# RGB_module.net
KiCad netlist of a schematic drawn in EAGLE
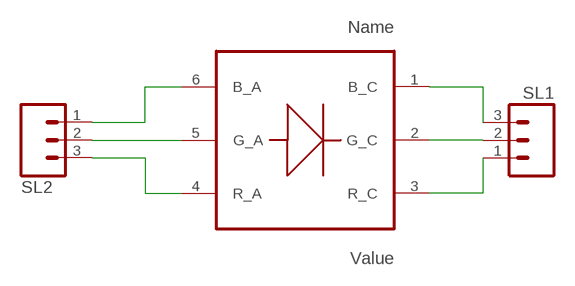
[diagram p0: schematic, sheet 1]

(export (version "E")
  (design (tool "Eeschema 10.0.6"))
  (components
    (comp (ref "RGB_MODULE")
      (value "RGB_SMD_3W")
      (footprint "eagle-import:RGB_SMD_6PIN")
      (libsource (lib "eagle-import") (part "RGB_SMD_3W"))
    )
    (comp (ref "SL1")
      (value "M03")
      (footprint "eagle-import:03P")
      (libsource (lib "eagle-import") (part "M03"))
    )
    (comp (ref "SL2")
      (value "M03")
      (footprint "eagle-import:03P")
      (libsource (lib "eagle-import") (part "M03"))
    )
  )
  (nets
    (net (code "1") (name "Net-(RGB_MODULE-B_A)") (class "Default")
      (node (ref "RGB_MODULE") (pin "6") (pinfunction "B_A_6") (pintype "passive"))
      (node (ref "SL2") (pin "1") (pinfunction "1_1") (pintype "passive"))
    )
    (net (code "2") (name "Net-(RGB_MODULE-B_C)") (class "Default")
      (node (ref "RGB_MODULE") (pin "1") (pinfunction "B_C_1") (pintype "passive"))
      (node (ref "SL1") (pin "3") (pinfunction "3_3") (pintype "passive"))
    )
    (net (code "3") (name "Net-(RGB_MODULE-G_A)") (class "Default")
      (node (ref "RGB_MODULE") (pin "5") (pinfunction "G_A_5") (pintype "passive"))
      (node (ref "SL2") (pin "2") (pinfunction "2_2") (pintype "passive"))
    )
    (net (code "4") (name "Net-(RGB_MODULE-G_C)") (class "Default")
      (node (ref "RGB_MODULE") (pin "2") (pinfunction "G_C_2") (pintype "passive"))
      (node (ref "SL1") (pin "2") (pinfunction "2_2") (pintype "passive"))
    )
    (net (code "5") (name "Net-(RGB_MODULE-R_A)") (class "Default")
      (node (ref "RGB_MODULE") (pin "4") (pinfunction "R_A_4") (pintype "passive"))
      (node (ref "SL2") (pin "3") (pinfunction "3_3") (pintype "passive"))
    )
    (net (code "6") (name "Net-(RGB_MODULE-R_C)") (class "Default")
      (node (ref "RGB_MODULE") (pin "3") (pinfunction "R_C_3") (pintype "passive"))
      (node (ref "SL1") (pin "1") (pinfunction "1_1") (pintype "passive"))
    )
  )
)
